# 202014A2232.net
KiCad netlist of a schematic drawn in Altium Designer
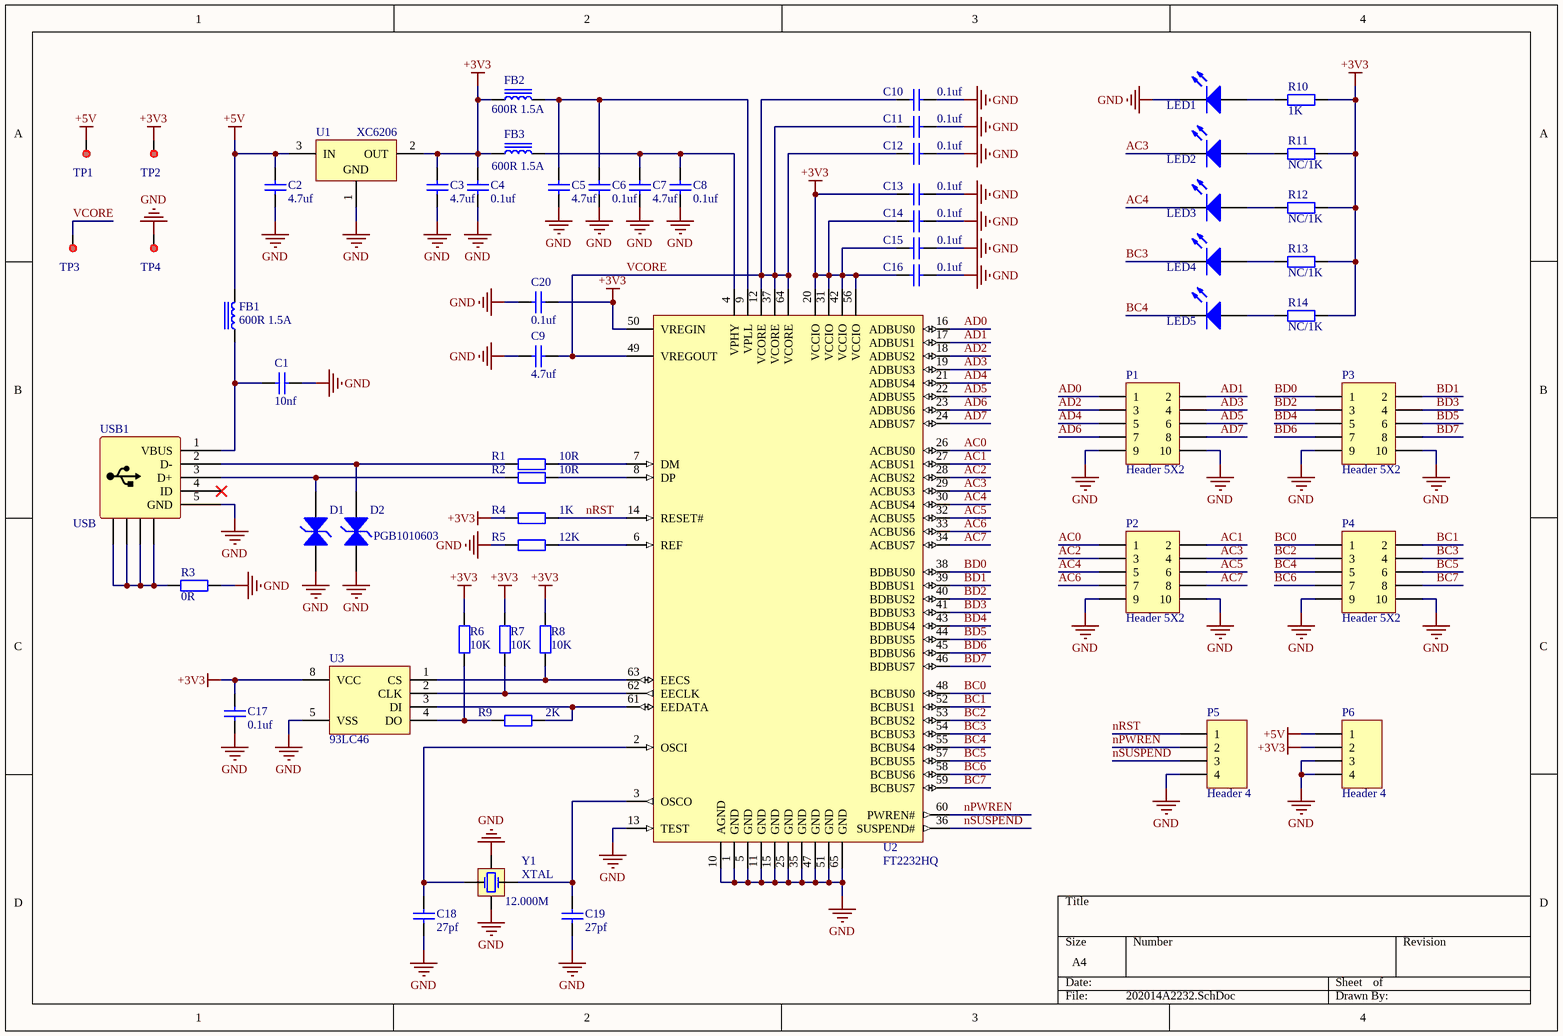
[diagram p0: 202014A2232.SchDoc]

(export (version "E")
  (design (tool "Eeschema 10.0.6"))
  (components
    (comp (ref "C1")
      (value "10nf")
      (footprint "C0805")
      (fields (field (name "Comment") "Cap"))
      (libsource (lib "carrot_lib") (part "Cap"))
    )
    (comp (ref "C2")
      (value "4.7uf")
      (footprint "C0805")
      (fields (field (name "Comment") "Cap"))
      (libsource (lib "carrot_lib") (part "Cap"))
    )
    (comp (ref "C3")
      (value "4.7uf")
      (footprint "C0805")
      (fields (field (name "Comment") "Cap"))
      (libsource (lib "carrot_lib") (part "Cap"))
    )
    (comp (ref "C4")
      (value "0.1uf")
      (footprint "C0805")
      (fields (field (name "Comment") "Cap"))
      (libsource (lib "carrot_lib") (part "Cap"))
    )
    (comp (ref "C5")
      (value "4.7uf")
      (footprint "C0805")
      (fields (field (name "Comment") "Cap"))
      (libsource (lib "carrot_lib") (part "Cap"))
    )
    (comp (ref "C6")
      (value "0.1uf")
      (footprint "C0805")
      (fields (field (name "Comment") "Cap"))
      (libsource (lib "carrot_lib") (part "Cap"))
    )
    (comp (ref "C7")
      (value "4.7uf")
      (footprint "C0805")
      (fields (field (name "Comment") "Cap"))
      (libsource (lib "carrot_lib") (part "Cap"))
    )
    (comp (ref "C8")
      (value "0.1uf")
      (footprint "C0805")
      (fields (field (name "Comment") "Cap"))
      (libsource (lib "carrot_lib") (part "Cap"))
    )
    (comp (ref "C9")
      (value "4.7uf")
      (footprint "C0805")
      (fields (field (name "Comment") "Cap"))
      (libsource (lib "carrot_lib") (part "Cap"))
    )
    (comp (ref "C10")
      (value "0.1uf")
      (footprint "C0805")
      (fields (field (name "Comment") "Cap"))
      (libsource (lib "carrot_lib") (part "Cap"))
    )
    (comp (ref "C11")
      (value "0.1uf")
      (footprint "C0805")
      (fields (field (name "Comment") "Cap"))
      (libsource (lib "carrot_lib") (part "Cap"))
    )
    (comp (ref "C12")
      (value "0.1uf")
      (footprint "C0805")
      (fields (field (name "Comment") "Cap"))
      (libsource (lib "carrot_lib") (part "Cap"))
    )
    (comp (ref "C13")
      (value "0.1uf")
      (footprint "C0805")
      (fields (field (name "Comment") "Cap"))
      (libsource (lib "carrot_lib") (part "Cap"))
    )
    (comp (ref "C14")
      (value "0.1uf")
      (footprint "C0805")
      (fields (field (name "Comment") "Cap"))
      (libsource (lib "carrot_lib") (part "Cap"))
    )
    (comp (ref "C15")
      (value "0.1uf")
      (footprint "C0805")
      (fields (field (name "Comment") "Cap"))
      (libsource (lib "carrot_lib") (part "Cap"))
    )
    (comp (ref "C16")
      (value "0.1uf")
      (footprint "C0805")
      (fields (field (name "Comment") "Cap"))
      (libsource (lib "carrot_lib") (part "Cap"))
    )
    (comp (ref "C17")
      (value "0.1uf")
      (footprint "C0805")
      (fields (field (name "Comment") "Cap"))
      (libsource (lib "carrot_lib") (part "Cap"))
    )
    (comp (ref "C18")
      (value "27pf")
      (footprint "C0805")
      (fields (field (name "Comment") "Cap"))
      (libsource (lib "carrot_lib") (part "Cap"))
    )
    (comp (ref "C19")
      (value "27pf")
      (footprint "C0805")
      (fields (field (name "Comment") "Cap"))
      (libsource (lib "carrot_lib") (part "Cap"))
    )
    (comp (ref "C20")
      (value "0.1uf")
      (footprint "C0805")
      (fields (field (name "Comment") "Cap"))
      (libsource (lib "carrot_lib") (part "Cap"))
    )
    (comp (ref "D1")
      (value "PGB1010603")
      (footprint "PGB1010603-0603")
      (description "Surface Mount Polymeric Electrostatic Discharge Suppressors")
      (libsource (lib "carrot_lib") (part "PGB1010603"))
    )
    (comp (ref "D2")
      (value "PGB1010603")
      (footprint "PGB1010603-0603")
      (description "Surface Mount Polymeric Electrostatic Discharge Suppressors")
      (libsource (lib "carrot_lib") (part "PGB1010603"))
    )
    (comp (ref "FB1")
      (value "600R 1.5A")
      (footprint "FB0805")
      (description "Ferrite Bead")
      (libsource (lib "carrot_lib") (part "Ferrite Bead"))
    )
    (comp (ref "FB2")
      (value "600R 1.5A")
      (footprint "FB0805")
      (description "Ferrite Bead")
      (libsource (lib "carrot_lib") (part "Ferrite Bead"))
    )
    (comp (ref "FB3")
      (value "600R 1.5A")
      (footprint "FB0805")
      (description "Ferrite Bead")
      (libsource (lib "carrot_lib") (part "Ferrite Bead"))
    )
    (comp (ref "LED1") (value "LED") (footprint "LED1206") (libsource (lib "carrot_lib") (part "LED")))
    (comp (ref "LED2") (value "LED") (footprint "LED1206") (libsource (lib "carrot_lib") (part "LED")))
    (comp (ref "LED3") (value "LED") (footprint "LED1206") (libsource (lib "carrot_lib") (part "LED")))
    (comp (ref "LED4") (value "LED") (footprint "LED1206") (libsource (lib "carrot_lib") (part "LED")))
    (comp (ref "LED5") (value "LED") (footprint "LED1206") (libsource (lib "carrot_lib") (part "LED")))
    (comp (ref "P1")
      (value "Header 5X2")
      (footprint "HDR2X5")
      (description "Header, 5-Pin, Dual row")
      (fields (field (name "PUBLISHER") "Altium Limited"))
      (libsource (lib "Miscellaneous Connectors") (part "Header 5X2"))
    )
    (comp (ref "P2")
      (value "Header 5X2")
      (footprint "HDR2X5")
      (description "Header, 5-Pin, Dual row")
      (fields (field (name "PUBLISHER") "Altium Limited"))
      (libsource (lib "Miscellaneous Connectors") (part "Header 5X2"))
    )
    (comp (ref "P3")
      (value "Header 5X2")
      (footprint "HDR2X5")
      (description "Header, 5-Pin, Dual row")
      (fields (field (name "PUBLISHER") "Altium Limited"))
      (libsource (lib "Miscellaneous Connectors") (part "Header 5X2"))
    )
    (comp (ref "P4")
      (value "Header 5X2")
      (footprint "HDR2X5")
      (description "Header, 5-Pin, Dual row")
      (fields (field (name "PUBLISHER") "Altium Limited"))
      (libsource (lib "Miscellaneous Connectors") (part "Header 5X2"))
    )
    (comp (ref "P5")
      (value "Header 4")
      (footprint "HDR1X4")
      (description "Header, 4-Pin")
      (fields (field (name "PUBLISHER") "Altium Limited"))
      (libsource (lib "Miscellaneous Connectors") (part "Header 4"))
    )
    (comp (ref "P6")
      (value "Header 4")
      (footprint "HDR1X4")
      (description "Header, 4-Pin")
      (fields (field (name "PUBLISHER") "Altium Limited"))
      (libsource (lib "Miscellaneous Connectors") (part "Header 4"))
    )
    (comp (ref "R1")
      (value "10R")
      (footprint "R0805")
      (description "电阻")
      (fields (field (name "Comment") "Res"))
      (libsource (lib "") (part "Res_2"))
    )
    (comp (ref "R2")
      (value "10R")
      (footprint "R0805")
      (description "电阻")
      (fields (field (name "Comment") "Res"))
      (libsource (lib "") (part "Res_2"))
    )
    (comp (ref "R3")
      (value "0R")
      (footprint "R0805")
      (description "电阻")
      (fields (field (name "Comment") "Res"))
      (libsource (lib "") (part "Res_2"))
    )
    (comp (ref "R4")
      (value "1K")
      (footprint "R0805")
      (description "电阻")
      (fields (field (name "Comment") "Res"))
      (libsource (lib "") (part "Res_2"))
    )
    (comp (ref "R5")
      (value "12K")
      (footprint "R0805")
      (description "电阻")
      (fields (field (name "Comment") "Res"))
      (libsource (lib "") (part "Res_2"))
    )
    (comp (ref "R6")
      (value "10K")
      (footprint "R0805")
      (description "电阻")
      (fields (field (name "Comment") "Res"))
      (libsource (lib "") (part "Res_1"))
    )
    (comp (ref "R7")
      (value "10K")
      (footprint "R0805")
      (description "电阻")
      (fields (field (name "Comment") "Res"))
      (libsource (lib "") (part "Res_1"))
    )
    (comp (ref "R8")
      (value "10K")
      (footprint "R0805")
      (description "电阻")
      (fields (field (name "Comment") "Res"))
      (libsource (lib "") (part "Res_1"))
    )
    (comp (ref "R9")
      (value "2K")
      (footprint "R0805")
      (description "电阻")
      (fields (field (name "Comment") "Res"))
      (libsource (lib "") (part "Res_2"))
    )
    (comp (ref "R10")
      (value "1K")
      (footprint "R0805")
      (description "电阻")
      (fields (field (name "Comment") "Res"))
      (libsource (lib "carrot_lib") (part "Res"))
    )
    (comp (ref "R11")
      (value "NC/1K")
      (footprint "R0805")
      (description "电阻")
      (fields (field (name "Comment") "Res"))
      (libsource (lib "carrot_lib") (part "Res"))
    )
    (comp (ref "R12")
      (value "NC/1K")
      (footprint "R0805")
      (description "电阻")
      (fields (field (name "Comment") "Res"))
      (libsource (lib "carrot_lib") (part "Res"))
    )
    (comp (ref "R13")
      (value "NC/1K")
      (footprint "R0805")
      (description "电阻")
      (fields (field (name "Comment") "Res"))
      (libsource (lib "carrot_lib") (part "Res"))
    )
    (comp (ref "R14")
      (value "NC/1K")
      (footprint "R0805")
      (description "电阻")
      (fields (field (name "Comment") "Res"))
      (libsource (lib "carrot_lib") (part "Res"))
    )
    (comp (ref "TP1")
      (value "TestPoint")
      (footprint "TestPoint-R30")
      (description "测试点")
      (libsource (lib "carrot_lib") (part "TestPoint"))
    )
    (comp (ref "TP2")
      (value "TestPoint")
      (footprint "TestPoint-R30")
      (description "测试点")
      (libsource (lib "carrot_lib") (part "TestPoint"))
    )
    (comp (ref "TP3")
      (value "TestPoint")
      (footprint "TestPoint-R30")
      (description "测试点")
      (libsource (lib "carrot_lib") (part "TestPoint"))
    )
    (comp (ref "TP4")
      (value "TestPoint")
      (footprint "TestPoint-R30")
      (description "测试点")
      (libsource (lib "carrot_lib") (part "TestPoint"))
    )
    (comp (ref "U1")
      (value "XC6206")
      (footprint "XC6206-SOT23")
      (description "Low ESR Cap. Compatible Positive Voltage Regulators")
      (libsource (lib "carrot_lib") (part "XC6206"))
    )
    (comp (ref "U2")
      (value "FT2232HQ")
      (footprint "FT2232HQ-QFN64")
      (description "Dual High Speed USB to Multipurpose UART/FIFO IC")
      (libsource (lib "carrot_lib") (part "FT2232HQ"))
    )
    (comp (ref "U3")
      (value "93LC46")
      (footprint "93LC46-SOIC8")
      (description "1K Microwire Compatible Serial EEPROM")
      (libsource (lib "carrot_lib") (part "93LC46"))
    )
    (comp (ref "USB1")
      (value "USB")
      (footprint "USB-Mini-SMT")
      (libsource (lib "carrot_lib") (part "USB-SHIELD"))
    )
    (comp (ref "Y1")
      (value "XTAL")
      (footprint "XTAL-3225")
      (description "无源晶振")
      (fields (field (name "ALTIUM_VALUE") "12.000M"))
      (libsource (lib "carrot_lib") (part "XTAL3"))
    )
  )
  (nets
    (net (code "1") (name "+3V3") (class "Default")
      (node (ref "C13") (pin "1") (pinfunction "1_1") (pintype "passive"))
      (node (ref "C14") (pin "1") (pinfunction "1_1") (pintype "passive"))
      (node (ref "C15") (pin "1") (pinfunction "1_1") (pintype "passive"))
      (node (ref "C16") (pin "1") (pinfunction "1_1") (pintype "passive"))
      (node (ref "C17") (pin "2") (pinfunction "2_2") (pintype "passive"))
      (node (ref "C20") (pin "1") (pinfunction "1_1") (pintype "passive"))
      (node (ref "C3") (pin "2") (pinfunction "2_2") (pintype "passive"))
      (node (ref "C4") (pin "2") (pinfunction "2_2") (pintype "passive"))
      (node (ref "FB2") (pin "1") (pinfunction "1_1") (pintype "passive"))
      (node (ref "FB3") (pin "1") (pinfunction "1_1") (pintype "passive"))
      (node (ref "P6") (pin "2") (pinfunction "2_2") (pintype "passive"))
      (node (ref "R10") (pin "1") (pinfunction "1_1") (pintype "passive"))
      (node (ref "R11") (pin "1") (pinfunction "1_1") (pintype "passive"))
      (node (ref "R12") (pin "1") (pinfunction "1_1") (pintype "passive"))
      (node (ref "R13") (pin "1") (pinfunction "1_1") (pintype "passive"))
      (node (ref "R14") (pin "1") (pinfunction "1_1") (pintype "passive"))
      (node (ref "R4") (pin "1") (pinfunction "1_1") (pintype "passive"))
      (node (ref "R6") (pin "2") (pinfunction "2_2") (pintype "passive"))
      (node (ref "R7") (pin "2") (pinfunction "2_2") (pintype "passive"))
      (node (ref "R8") (pin "2") (pinfunction "2_2") (pintype "passive"))
      (node (ref "TP2") (pin "1") (pinfunction "1_1") (pintype "passive"))
      (node (ref "U1") (pin "2") (pinfunction "OUT_2") (pintype "passive"))
      (node (ref "U2") (pin "20") (pinfunction "VCCIO_20") (pintype "power_in"))
      (node (ref "U2") (pin "31") (pinfunction "VCCIO_31") (pintype "power_in"))
      (node (ref "U2") (pin "42") (pinfunction "VCCIO_42") (pintype "power_in"))
      (node (ref "U2") (pin "50") (pinfunction "VREGIN_50") (pintype "power_in"))
      (node (ref "U2") (pin "56") (pinfunction "VCCIO_56") (pintype "power_in"))
      (node (ref "U3") (pin "8") (pinfunction "VCC_8") (pintype "passive"))
    )
    (net (code "2") (name "+5V") (class "Default")
      (node (ref "C2") (pin "2") (pinfunction "2_2") (pintype "passive"))
      (node (ref "FB1") (pin "2") (pinfunction "2_2") (pintype "passive"))
      (node (ref "P6") (pin "1") (pinfunction "1_1") (pintype "passive"))
      (node (ref "TP1") (pin "1") (pinfunction "1_1") (pintype "passive"))
      (node (ref "U1") (pin "3") (pinfunction "IN_3") (pintype "passive"))
    )
    (net (code "3") (name "/AC0") (class "Default")
      (node (ref "P2") (pin "1") (pinfunction "1_1") (pintype "passive"))
      (node (ref "U2") (pin "26") (pinfunction "ACBUS0_26") (pintype "bidirectional"))
    )
    (net (code "4") (name "/AC1") (class "Default")
      (node (ref "P2") (pin "2") (pinfunction "2_2") (pintype "passive"))
      (node (ref "U2") (pin "27") (pinfunction "ACBUS1_27") (pintype "bidirectional"))
    )
    (net (code "5") (name "/AC2") (class "Default")
      (node (ref "P2") (pin "3") (pinfunction "3_3") (pintype "passive"))
      (node (ref "U2") (pin "28") (pinfunction "ACBUS2_28") (pintype "bidirectional"))
    )
    (net (code "6") (name "/AC3") (class "Default")
      (node (ref "LED2") (pin "2") (pinfunction "K_2") (pintype "passive"))
      (node (ref "P2") (pin "4") (pinfunction "4_4") (pintype "passive"))
      (node (ref "U2") (pin "29") (pinfunction "ACBUS3_29") (pintype "bidirectional"))
    )
    (net (code "7") (name "/AC4") (class "Default")
      (node (ref "LED3") (pin "2") (pinfunction "K_2") (pintype "passive"))
      (node (ref "P2") (pin "5") (pinfunction "5_5") (pintype "passive"))
      (node (ref "U2") (pin "30") (pinfunction "ACBUS4_30") (pintype "bidirectional"))
    )
    (net (code "8") (name "/AC5") (class "Default")
      (node (ref "P2") (pin "6") (pinfunction "6_6") (pintype "passive"))
      (node (ref "U2") (pin "32") (pinfunction "ACBUS5_32") (pintype "bidirectional"))
    )
    (net (code "9") (name "/AC6") (class "Default")
      (node (ref "P2") (pin "7") (pinfunction "7_7") (pintype "passive"))
      (node (ref "U2") (pin "33") (pinfunction "ACBUS6_33") (pintype "bidirectional"))
    )
    (net (code "10") (name "/AC7") (class "Default")
      (node (ref "P2") (pin "8") (pinfunction "8_8") (pintype "passive"))
      (node (ref "U2") (pin "34") (pinfunction "ACBUS7_34") (pintype "bidirectional"))
    )
    (net (code "11") (name "/AD0") (class "Default")
      (node (ref "P1") (pin "1") (pinfunction "1_1") (pintype "passive"))
      (node (ref "U2") (pin "16") (pinfunction "ADBUS0_16") (pintype "bidirectional"))
    )
    (net (code "12") (name "/AD1") (class "Default")
      (node (ref "P1") (pin "2") (pinfunction "2_2") (pintype "passive"))
      (node (ref "U2") (pin "17") (pinfunction "ADBUS1_17") (pintype "bidirectional"))
    )
    (net (code "13") (name "/AD2") (class "Default")
      (node (ref "P1") (pin "3") (pinfunction "3_3") (pintype "passive"))
      (node (ref "U2") (pin "18") (pinfunction "ADBUS2_18") (pintype "bidirectional"))
    )
    (net (code "14") (name "/AD3") (class "Default")
      (node (ref "P1") (pin "4") (pinfunction "4_4") (pintype "passive"))
      (node (ref "U2") (pin "19") (pinfunction "ADBUS3_19") (pintype "bidirectional"))
    )
    (net (code "15") (name "/AD4") (class "Default")
      (node (ref "P1") (pin "5") (pinfunction "5_5") (pintype "passive"))
      (node (ref "U2") (pin "21") (pinfunction "ADBUS4_21") (pintype "bidirectional"))
    )
    (net (code "16") (name "/AD5") (class "Default")
      (node (ref "P1") (pin "6") (pinfunction "6_6") (pintype "passive"))
      (node (ref "U2") (pin "22") (pinfunction "ADBUS5_22") (pintype "bidirectional"))
    )
    (net (code "17") (name "/AD6") (class "Default")
      (node (ref "P1") (pin "7") (pinfunction "7_7") (pintype "passive"))
      (node (ref "U2") (pin "23") (pinfunction "ADBUS6_23") (pintype "bidirectional"))
    )
    (net (code "18") (name "/AD7") (class "Default")
      (node (ref "P1") (pin "8") (pinfunction "8_8") (pintype "passive"))
      (node (ref "U2") (pin "24") (pinfunction "ADBUS7_24") (pintype "bidirectional"))
    )
    (net (code "19") (name "/BC0") (class "Default")
      (node (ref "P4") (pin "1") (pinfunction "1_1") (pintype "passive"))
      (node (ref "U2") (pin "48") (pinfunction "BCBUS0_48") (pintype "bidirectional"))
    )
    (net (code "20") (name "/BC1") (class "Default")
      (node (ref "P4") (pin "2") (pinfunction "2_2") (pintype "passive"))
      (node (ref "U2") (pin "52") (pinfunction "BCBUS1_52") (pintype "bidirectional"))
    )
    (net (code "21") (name "/BC2") (class "Default")
      (node (ref "P4") (pin "3") (pinfunction "3_3") (pintype "passive"))
      (node (ref "U2") (pin "53") (pinfunction "BCBUS2_53") (pintype "bidirectional"))
    )
    (net (code "22") (name "/BC3") (class "Default")
      (node (ref "LED4") (pin "2") (pinfunction "K_2") (pintype "passive"))
      (node (ref "P4") (pin "4") (pinfunction "4_4") (pintype "passive"))
      (node (ref "U2") (pin "54") (pinfunction "BCBUS3_54") (pintype "bidirectional"))
    )
    (net (code "23") (name "/BC4") (class "Default")
      (node (ref "LED5") (pin "2") (pinfunction "K_2") (pintype "passive"))
      (node (ref "P4") (pin "5") (pinfunction "5_5") (pintype "passive"))
      (node (ref "U2") (pin "55") (pinfunction "BCBUS4_55") (pintype "bidirectional"))
    )
    (net (code "24") (name "/BC5") (class "Default")
      (node (ref "P4") (pin "6") (pinfunction "6_6") (pintype "passive"))
      (node (ref "U2") (pin "57") (pinfunction "BCBUS5_57") (pintype "bidirectional"))
    )
    (net (code "25") (name "/BC6") (class "Default")
      (node (ref "P4") (pin "7") (pinfunction "7_7") (pintype "passive"))
      (node (ref "U2") (pin "58") (pinfunction "BCBUS6_58") (pintype "bidirectional"))
    )
    (net (code "26") (name "/BC7") (class "Default")
      (node (ref "P4") (pin "8") (pinfunction "8_8") (pintype "passive"))
      (node (ref "U2") (pin "59") (pinfunction "BCBUS7_59") (pintype "bidirectional"))
    )
    (net (code "27") (name "/BD0") (class "Default")
      (node (ref "P3") (pin "1") (pinfunction "1_1") (pintype "passive"))
      (node (ref "U2") (pin "38") (pinfunction "BDBUS0_38") (pintype "bidirectional"))
    )
    (net (code "28") (name "/BD1") (class "Default")
      (node (ref "P3") (pin "2") (pinfunction "2_2") (pintype "passive"))
      (node (ref "U2") (pin "39") (pinfunction "BDBUS1_39") (pintype "bidirectional"))
    )
    (net (code "29") (name "/BD2") (class "Default")
      (node (ref "P3") (pin "3") (pinfunction "3_3") (pintype "passive"))
      (node (ref "U2") (pin "40") (pinfunction "BDBUS2_40") (pintype "bidirectional"))
    )
    (net (code "30") (name "/BD3") (class "Default")
      (node (ref "P3") (pin "4") (pinfunction "4_4") (pintype "passive"))
      (node (ref "U2") (pin "41") (pinfunction "BDBUS3_41") (pintype "bidirectional"))
    )
    (net (code "31") (name "/BD4") (class "Default")
      (node (ref "P3") (pin "5") (pinfunction "5_5") (pintype "passive"))
      (node (ref "U2") (pin "43") (pinfunction "BDBUS4_43") (pintype "bidirectional"))
    )
    (net (code "32") (name "/BD5") (class "Default")
      (node (ref "P3") (pin "6") (pinfunction "6_6") (pintype "passive"))
      (node (ref "U2") (pin "44") (pinfunction "BDBUS5_44") (pintype "bidirectional"))
    )
    (net (code "33") (name "/BD6") (class "Default")
      (node (ref "P3") (pin "7") (pinfunction "7_7") (pintype "passive"))
      (node (ref "U2") (pin "45") (pinfunction "BDBUS6_45") (pintype "bidirectional"))
    )
    (net (code "34") (name "/BD7") (class "Default")
      (node (ref "P3") (pin "8") (pinfunction "8_8") (pintype "passive"))
      (node (ref "U2") (pin "46") (pinfunction "BDBUS7_46") (pintype "bidirectional"))
    )
    (net (code "35") (name "/VCORE") (class "Default")
      (node (ref "C10") (pin "1") (pinfunction "1_1") (pintype "passive"))
      (node (ref "C11") (pin "1") (pinfunction "1_1") (pintype "passive"))
      (node (ref "C12") (pin "1") (pinfunction "1_1") (pintype "passive"))
      (node (ref "C9") (pin "2") (pinfunction "2_2") (pintype "passive"))
      (node (ref "TP3") (pin "1") (pinfunction "1_1") (pintype "passive"))
      (node (ref "U2") (pin "12") (pinfunction "VCORE_12") (pintype "power_in"))
      (node (ref "U2") (pin "37") (pinfunction "VCORE_37") (pintype "power_in"))
      (node (ref "U2") (pin "49") (pinfunction "VREGOUT_49") (pintype "power_in"))
      (node (ref "U2") (pin "64") (pinfunction "VCORE_64") (pintype "power_in"))
    )
    (net (code "36") (name "/nPWREN") (class "Default")
      (node (ref "P5") (pin "2") (pinfunction "2_2") (pintype "passive"))
      (node (ref "U2") (pin "60") (pinfunction "PWREN#_60") (pintype "output"))
    )
    (net (code "37") (name "/nRST") (class "Default")
      (node (ref "P5") (pin "1") (pinfunction "1_1") (pintype "passive"))
      (node (ref "R4") (pin "2") (pinfunction "2_2") (pintype "passive"))
      (node (ref "U2") (pin "14") (pinfunction "RESET#_14") (pintype "input"))
    )
    (net (code "38") (name "/nSUSPEND") (class "Default")
      (node (ref "P5") (pin "3") (pinfunction "3_3") (pintype "passive"))
      (node (ref "U2") (pin "36") (pinfunction "SUSPEND#_36") (pintype "output"))
    )
    (net (code "39") (name "GND") (class "Default")
      (node (ref "C1") (pin "2") (pinfunction "2_2") (pintype "passive"))
      (node (ref "C10") (pin "2") (pinfunction "2_2") (pintype "passive"))
      (node (ref "C11") (pin "2") (pinfunction "2_2") (pintype "passive"))
      (node (ref "C12") (pin "2") (pinfunction "2_2") (pintype "passive"))
      (node (ref "C13") (pin "2") (pinfunction "2_2") (pintype "passive"))
      (node (ref "C14") (pin "2") (pinfunction "2_2") (pintype "passive"))
      (node (ref "C15") (pin "2") (pinfunction "2_2") (pintype "passive"))
      (node (ref "C16") (pin "2") (pinfunction "2_2") (pintype "passive"))
      (node (ref "C17") (pin "1") (pinfunction "1_1") (pintype "passive"))
      (node (ref "C18") (pin "1") (pinfunction "1_1") (pintype "passive"))
      (node (ref "C19") (pin "1") (pinfunction "1_1") (pintype "passive"))
      (node (ref "C2") (pin "1") (pinfunction "1_1") (pintype "passive"))
      (node (ref "C20") (pin "2") (pinfunction "2_2") (pintype "passive"))
      (node (ref "C3") (pin "1") (pinfunction "1_1") (pintype "passive"))
      (node (ref "C4") (pin "1") (pinfunction "1_1") (pintype "passive"))
      (node (ref "C5") (pin "1") (pinfunction "1_1") (pintype "passive"))
      (node (ref "C6") (pin "1") (pinfunction "1_1") (pintype "passive"))
      (node (ref "C7") (pin "1") (pinfunction "1_1") (pintype "passive"))
      (node (ref "C8") (pin "1") (pinfunction "1_1") (pintype "passive"))
      (node (ref "C9") (pin "1") (pinfunction "1_1") (pintype "passive"))
      (node (ref "D1") (pin "1") (pinfunction "1_1") (pintype "passive"))
      (node (ref "D2") (pin "1") (pinfunction "1_1") (pintype "passive"))
      (node (ref "LED1") (pin "2") (pinfunction "K_2") (pintype "passive"))
      (node (ref "P1") (pin "10") (pinfunction "10_10") (pintype "passive"))
      (node (ref "P1") (pin "9") (pinfunction "9_9") (pintype "passive"))
      (node (ref "P2") (pin "10") (pinfunction "10_10") (pintype "passive"))
      (node (ref "P2") (pin "9") (pinfunction "9_9") (pintype "passive"))
      (node (ref "P3") (pin "10") (pinfunction "10_10") (pintype "passive"))
      (node (ref "P3") (pin "9") (pinfunction "9_9") (pintype "passive"))
      (node (ref "P4") (pin "10") (pinfunction "10_10") (pintype "passive"))
      (node (ref "P4") (pin "9") (pinfunction "9_9") (pintype "passive"))
      (node (ref "P5") (pin "4") (pinfunction "4_4") (pintype "passive"))
      (node (ref "P6") (pin "3") (pinfunction "3_3") (pintype "passive"))
      (node (ref "P6") (pin "4") (pinfunction "4_4") (pintype "passive"))
      (node (ref "R3") (pin "2") (pinfunction "2_2") (pintype "passive"))
      (node (ref "R5") (pin "1") (pinfunction "1_1") (pintype "passive"))
      (node (ref "TP4") (pin "1") (pinfunction "1_1") (pintype "passive"))
      (node (ref "U1") (pin "1") (pinfunction "GND_1") (pintype "passive"))
      (node (ref "U2") (pin "1") (pinfunction "GND_1") (pintype "power_in"))
      (node (ref "U2") (pin "10") (pinfunction "AGND_10") (pintype "power_in"))
      (node (ref "U2") (pin "11") (pinfunction "GND_11") (pintype "power_in"))
      (node (ref "U2") (pin "13") (pinfunction "TEST_13") (pintype "input"))
      (node (ref "U2") (pin "15") (pinfunction "GND_15") (pintype "power_in"))
      (node (ref "U2") (pin "25") (pinfunction "GND_25") (pintype "power_in"))
      (node (ref "U2") (pin "35") (pinfunction "GND_35") (pintype "power_in"))
      (node (ref "U2") (pin "47") (pinfunction "GND_47") (pintype "power_in"))
      (node (ref "U2") (pin "5") (pinfunction "GND_5") (pintype "power_in"))
      (node (ref "U2") (pin "51") (pinfunction "GND_51") (pintype "power_in"))
      (node (ref "U2") (pin "65") (pinfunction "GND_65") (pintype "power_in"))
      (node (ref "U3") (pin "5") (pinfunction "VSS_5") (pintype "passive"))
      (node (ref "USB1") (pin "5") (pinfunction "GND_5") (pintype "passive"))
      (node (ref "Y1") (pin "2") (pinfunction "GND_2") (pintype "passive"))
      (node (ref "Y1") (pin "4") (pinfunction "GND_4") (pintype "passive"))
    )
    (net (code "40") (name "Net-(LED1-A)") (class "Default")
      (node (ref "LED1") (pin "1") (pinfunction "A_1") (pintype "passive"))
      (node (ref "R10") (pin "2") (pinfunction "2_2") (pintype "passive"))
    )
    (net (code "41") (name "Net-(LED2-A)") (class "Default")
      (node (ref "LED2") (pin "1") (pinfunction "A_1") (pintype "passive"))
      (node (ref "R11") (pin "2") (pinfunction "2_2") (pintype "passive"))
    )
    (net (code "42") (name "Net-(LED3-A)") (class "Default")
      (node (ref "LED3") (pin "1") (pinfunction "A_1") (pintype "passive"))
      (node (ref "R12") (pin "2") (pinfunction "2_2") (pintype "passive"))
    )
    (net (code "43") (name "Net-(LED4-A)") (class "Default")
      (node (ref "LED4") (pin "1") (pinfunction "A_1") (pintype "passive"))
      (node (ref "R13") (pin "2") (pinfunction "2_2") (pintype "passive"))
    )
    (net (code "44") (name "Net-(LED5-A)") (class "Default")
      (node (ref "LED5") (pin "1") (pinfunction "A_1") (pintype "passive"))
      (node (ref "R14") (pin "2") (pinfunction "2_2") (pintype "passive"))
    )
    (net (code "45") (name "Net-(R3-Pad1)") (class "Default")
      (node (ref "R3") (pin "1") (pinfunction "1_1") (pintype "passive"))
      (node (ref "USB1") (pin "6") (pinfunction "6_6") (pintype "passive"))
      (node (ref "USB1") (pin "7") (pinfunction "7_7") (pintype "passive"))
      (node (ref "USB1") (pin "8") (pinfunction "8_8") (pintype "passive"))
      (node (ref "USB1") (pin "9") (pinfunction "9_9") (pintype "passive"))
    )
    (net (code "46") (name "Net-(U2-DM)") (class "Default")
      (node (ref "R1") (pin "2") (pinfunction "2_2") (pintype "passive"))
      (node (ref "U2") (pin "7") (pinfunction "DM_7") (pintype "input"))
    )
    (net (code "47") (name "Net-(U2-DP)") (class "Default")
      (node (ref "R2") (pin "2") (pinfunction "2_2") (pintype "passive"))
      (node (ref "U2") (pin "8") (pinfunction "DP_8") (pintype "input"))
    )
    (net (code "48") (name "Net-(U2-EECLK)") (class "Default")
      (node (ref "R7") (pin "1") (pinfunction "1_1") (pintype "passive"))
      (node (ref "U2") (pin "62") (pinfunction "EECLK_62") (pintype "output"))
      (node (ref "U3") (pin "2") (pinfunction "CLK_2") (pintype "passive"))
    )
    (net (code "49") (name "Net-(U2-EECS)") (class "Default")
      (node (ref "R8") (pin "1") (pinfunction "1_1") (pintype "passive"))
      (node (ref "U2") (pin "63") (pinfunction "EECS_63") (pintype "bidirectional"))
      (node (ref "U3") (pin "1") (pinfunction "CS_1") (pintype "passive"))
    )
    (net (code "50") (name "Net-(U2-EEDATA)") (class "Default")
      (node (ref "R9") (pin "2") (pinfunction "2_2") (pintype "passive"))
      (node (ref "U2") (pin "61") (pinfunction "EEDATA_61") (pintype "bidirectional"))
      (node (ref "U3") (pin "3") (pinfunction "DI_3") (pintype "passive"))
    )
    (net (code "51") (name "Net-(U2-OSCI)") (class "Default")
      (node (ref "C18") (pin "2") (pinfunction "2_2") (pintype "passive"))
      (node (ref "U2") (pin "2") (pinfunction "OSCI_2") (pintype "input"))
      (node (ref "Y1") (pin "1") (pinfunction "OSC1_1") (pintype "passive"))
    )
    (net (code "52") (name "Net-(U2-OSCO)") (class "Default")
      (node (ref "C19") (pin "2") (pinfunction "2_2") (pintype "passive"))
      (node (ref "U2") (pin "3") (pinfunction "OSCO_3") (pintype "output"))
      (node (ref "Y1") (pin "3") (pinfunction "OSC2_3") (pintype "passive"))
    )
    (net (code "53") (name "Net-(U2-REF)") (class "Default")
      (node (ref "R5") (pin "2") (pinfunction "2_2") (pintype "passive"))
      (node (ref "U2") (pin "6") (pinfunction "REF_6") (pintype "input"))
    )
    (net (code "54") (name "Net-(U2-VPHY)") (class "Default")
      (node (ref "C7") (pin "2") (pinfunction "2_2") (pintype "passive"))
      (node (ref "C8") (pin "2") (pinfunction "2_2") (pintype "passive"))
      (node (ref "FB3") (pin "2") (pinfunction "2_2") (pintype "passive"))
      (node (ref "U2") (pin "4") (pinfunction "VPHY_4") (pintype "power_in"))
    )
    (net (code "55") (name "Net-(U2-VPLL)") (class "Default")
      (node (ref "C5") (pin "2") (pinfunction "2_2") (pintype "passive"))
      (node (ref "C6") (pin "2") (pinfunction "2_2") (pintype "passive"))
      (node (ref "FB2") (pin "2") (pinfunction "2_2") (pintype "passive"))
      (node (ref "U2") (pin "9") (pinfunction "VPLL_9") (pintype "power_in"))
    )
    (net (code "56") (name "Net-(U3-DO)") (class "Default")
      (node (ref "R6") (pin "1") (pinfunction "1_1") (pintype "passive"))
      (node (ref "R9") (pin "1") (pinfunction "1_1") (pintype "passive"))
      (node (ref "U3") (pin "4") (pinfunction "DO_4") (pintype "passive"))
    )
    (net (code "57") (name "Net-(USB1-D+)") (class "Default")
      (node (ref "D1") (pin "2") (pinfunction "2_2") (pintype "passive"))
      (node (ref "R2") (pin "1") (pinfunction "1_1") (pintype "passive"))
      (node (ref "USB1") (pin "3") (pinfunction "D+_3") (pintype "passive"))
    )
    (net (code "58") (name "Net-(USB1-D-)") (class "Default")
      (node (ref "D2") (pin "2") (pinfunction "2_2") (pintype "passive"))
      (node (ref "R1") (pin "1") (pinfunction "1_1") (pintype "passive"))
      (node (ref "USB1") (pin "2") (pinfunction "D-_2") (pintype "passive"))
    )
    (net (code "59") (name "Net-(USB1-VBUS)") (class "Default")
      (node (ref "C1") (pin "1") (pinfunction "1_1") (pintype "passive"))
      (node (ref "FB1") (pin "1") (pinfunction "1_1") (pintype "passive"))
      (node (ref "USB1") (pin "1") (pinfunction "VBUS_1") (pintype "passive"))
    )
    (net (code "60") (name "unconnected-(USB1-ID-Pad4)") (class "Default")
      (node (ref "USB1") (pin "4") (pinfunction "ID_4") (pintype "passive+no_connect"))
    )
  )
)
